# PM12_P5V5.net
KiCad netlist of a schematic drawn in Altium Designer
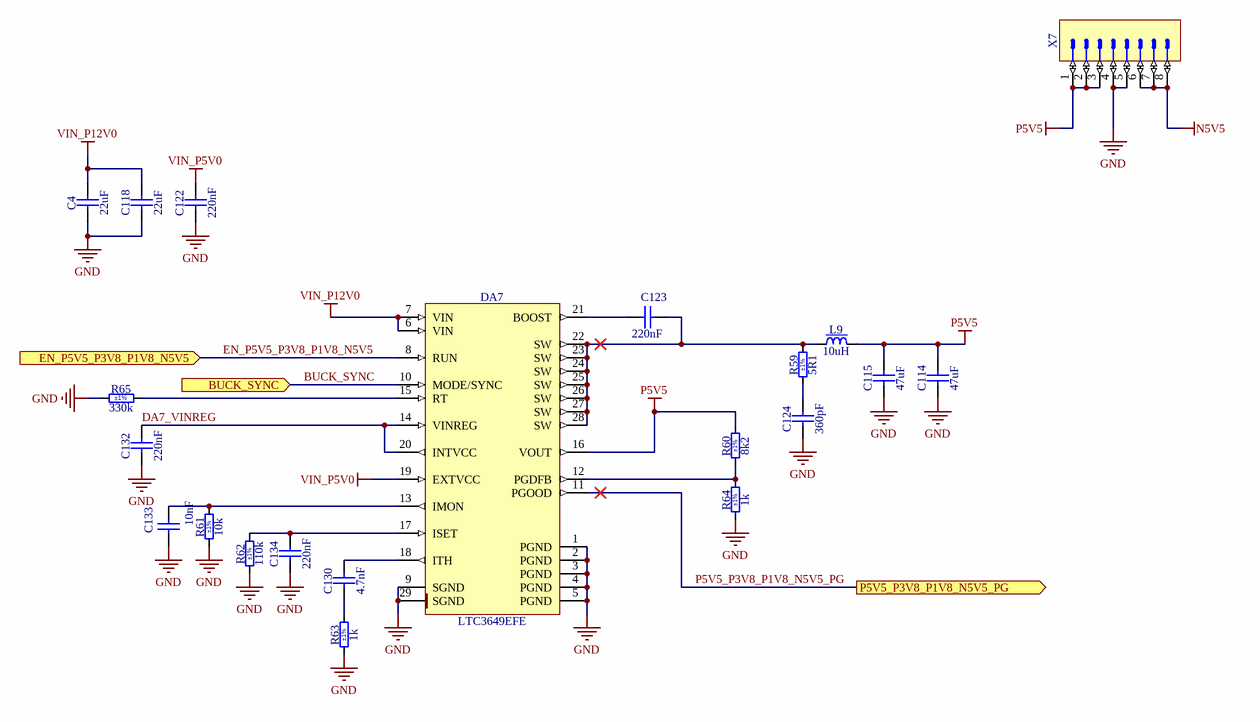
[diagram p0: PM12_P5V5.SchDoc]

(export (version "E")
  (design (tool "Eeschema 10.0.6"))
  (components
    (comp (ref "C4")
      (value "22uF")
      (footprint "CAPC3216X180N")
      (description "Non-polarised capacitor")
      (fields
        (field (name "PART NUMBER") "CC1206_22UF_25V_20%_X5R")
        (field (name "VOLTAGE") "25V")
        (field (name "AUTHOR") "CERN DEM WB")
      )
      (libsource (lib "Capacitors") (part "Capacitor - non polarized"))
    )
    (comp (ref "C114")
      (value "47uF")
      (footprint "CAPC3225X270N")
      (description "Non-polarised capacitor")
      (fields
        (field (name "PART NUMBER") "CC1210_47UF_16V_20%_X5R")
        (field (name "VOLTAGE") "16V")
        (field (name "AUTHOR") "CERN DEM MR")
      )
      (libsource (lib "Capacitors") (part "Capacitor - non polarized"))
    )
    (comp (ref "C115")
      (value "47uF")
      (footprint "CAPC3225X270N")
      (description "Non-polarised capacitor")
      (fields
        (field (name "PART NUMBER") "CC1210_47UF_16V_20%_X5R")
        (field (name "VOLTAGE") "16V")
        (field (name "AUTHOR") "CERN DEM MR")
      )
      (libsource (lib "Capacitors") (part "Capacitor - non polarized"))
    )
    (comp (ref "C118")
      (value "22uF")
      (footprint "CAPC3216X180N")
      (description "Non-polarised capacitor")
      (fields
        (field (name "PART NUMBER") "CC1206_22UF_25V_20%_X5R")
        (field (name "VOLTAGE") "25V")
        (field (name "AUTHOR") "CERN DEM WB")
      )
      (libsource (lib "Capacitors") (part "Capacitor - non polarized"))
    )
    (comp (ref "C122")
      (value "220nF")
      (footprint "CAPC2012X135N")
      (description "Non-polarised capacitor")
      (fields
        (field (name "PART NUMBER") "CC0805_220NF_50V_10%_X7R")
        (field (name "VOLTAGE") "50V")
        (field (name "AUTHOR") "CERN DEM JLC")
      )
      (libsource (lib "Capacitors") (part "Capacitor - non polarized"))
    )
    (comp (ref "C123")
      (value "220nF")
      (footprint "CAPC2012X135N")
      (description "Non-polarised capacitor")
      (fields
        (field (name "PART NUMBER") "CC0805_220NF_50V_10%_X7R")
        (field (name "VOLTAGE") "50V")
        (field (name "AUTHOR") "CERN DEM JLC")
      )
      (libsource (lib "Capacitors") (part "Capacitor - non polarized"))
    )
    (comp (ref "C124")
      (value "360pF")
      (footprint "CAPC2013X145N")
      (description "Non-polarised capacitor")
      (fields
        (field (name "PART NUMBER") "CC0805_360PF_50V_5%_C0G")
        (field (name "VOLTAGE") "50V")
        (field (name "AUTHOR") "CERN DEM HF")
      )
      (libsource (lib "Capacitors") (part "Capacitor - non polarized"))
    )
    (comp (ref "C130")
      (value "4.7nF")
      (footprint "CAPC2012X135N")
      (description "Non-polarised capacitor")
      (fields
        (field (name "PART NUMBER") "CC0805_4.7NF_50V_10%_X7R")
        (field (name "VOLTAGE") "50V")
        (field (name "AUTHOR") "CERN DEM JLC")
      )
      (libsource (lib "Capacitors") (part "Capacitor - non polarized"))
    )
    (comp (ref "C132")
      (value "220nF")
      (footprint "CAPC2012X135N")
      (description "Non-polarised capacitor")
      (fields
        (field (name "PART NUMBER") "CC0805_220NF_50V_10%_X7R")
        (field (name "VOLTAGE") "50V")
        (field (name "AUTHOR") "CERN DEM JLC")
      )
      (libsource (lib "Capacitors") (part "Capacitor - non polarized"))
    )
    (comp (ref "C133")
      (value "10nF")
      (footprint "CAPC1005X55N")
      (description "Non-polarised capacitor")
      (fields
        (field (name "PART NUMBER") "CC0402_10NF_25V_10%_X7R")
        (field (name "VOLTAGE") "25V")
        (field (name "AUTHOR") "CERN DEM JLC")
      )
      (libsource (lib "Capacitors") (part "Capacitor - non polarized"))
    )
    (comp (ref "C134")
      (value "220nF")
      (footprint "CAPC2012X135N")
      (description "Non-polarised capacitor")
      (fields
        (field (name "PART NUMBER") "CC0805_220NF_50V_10%_X7R")
        (field (name "VOLTAGE") "50V")
        (field (name "AUTHOR") "CERN DEM JLC")
      )
      (libsource (lib "Capacitors") (part "Capacitor - non polarized"))
    )
    (comp (ref "DA7")
      (value "LTC3649EFE")
      (footprint "SOP65P640X120-29N-R274X475")
      (description "60V, 4A Synchronous Step-Down Regulator with Rail-to-Rail Programmable Output")
      (fields (field (name "MANUFACTURER") "LINEAR TECHNOLOGY") (field (name "AUTHOR") "CERN DEM HF"))
      (libsource (lib "ICs And Semiconductors") (part "LTC3649XFE"))
    )
    (comp (ref "L9")
      (value "10uH")
      (footprint "IND_VISHAY_IHPL4040DZ-01")
      (description "Inductor With Core")
      (fields
        (field (name "PART NUMBER") "IND4040_10UH_20%_VISHAY_IHLP-4040DZ-01")
        (field (name "POWER") "6.8A")
        (field (name "AUTHOR") "CERN DEM HF")
      )
      (libsource (lib "Inductors & Transformers") (part "Inductor With Magnetic core"))
    )
    (comp (ref "R59")
      (value "5R1")
      (footprint "RESC2012X60N")
      (description "Resistor - 1%")
      (fields
        (field (name "TOLERANCE") "±1%")
        (field (name "PART NUMBER") "R0805_5R1_1%_0.125W_100PPM")
        (field (name "POWER") "0.125W")
        (field (name "AUTHOR") "CERN DEM HF")
      )
      (libsource (lib "Resistors") (part "Resistor - 1%"))
    )
    (comp (ref "R60")
      (value "8k2")
      (footprint "RESC2012X60N")
      (description "Resistor - 1%")
      (fields
        (field (name "TOLERANCE") "±1%")
        (field (name "PART NUMBER") "R0805_8K2_1%_0.125W_100PPM")
        (field (name "POWER") "0.125W")
        (field (name "AUTHOR") "CERN DEM JLC")
      )
      (libsource (lib "Resistors") (part "Resistor - 1%"))
    )
    (comp (ref "R61")
      (value "10k")
      (footprint "RESC1608X55N")
      (description "Resistor - 1%")
      (fields
        (field (name "TOLERANCE") "±1%")
        (field (name "PART NUMBER") "R0603_10K_1%_0.1W_100PPM")
        (field (name "POWER") "0.1W")
        (field (name "AUTHOR") "CERN DEM JLC")
      )
      (libsource (lib "Resistors") (part "Resistor - 1%"))
    )
    (comp (ref "R62")
      (value "110k")
      (footprint "RESC2012X60N")
      (description "Resistor - 1%")
      (fields
        (field (name "TOLERANCE") "±1%")
        (field (name "PART NUMBER") "R0805_110K_1%_0.125W_100PPM")
        (field (name "POWER") "0.125W")
        (field (name "AUTHOR") "CERN DEM JLC")
      )
      (libsource (lib "Resistors") (part "Resistor - 1%"))
    )
    (comp (ref "R63")
      (value "1k")
      (footprint "RESC1005X40N")
      (description "Resistor - 1%")
      (fields
        (field (name "TOLERANCE") "±1%")
        (field (name "PART NUMBER") "R0402_1K_1%_0.0625W_100PPM")
        (field (name "POWER") "0.0625W")
        (field (name "AUTHOR") "CERN DEM JLC")
      )
      (libsource (lib "Resistors") (part "Resistor - 1%"))
    )
    (comp (ref "R64")
      (value "1k")
      (footprint "RESC1005X40N")
      (description "Resistor - 1%")
      (fields
        (field (name "TOLERANCE") "±1%")
        (field (name "PART NUMBER") "R0402_1K_1%_0.0625W_100PPM")
        (field (name "POWER") "0.0625W")
        (field (name "AUTHOR") "CERN DEM JLC")
      )
      (libsource (lib "Resistors") (part "Resistor - 1%"))
    )
    (comp (ref "R65")
      (value "330k")
      (footprint "RESC2012X60N")
      (description "Resistor - 1%")
      (fields
        (field (name "TOLERANCE") "±1%")
        (field (name "PART NUMBER") "R0805_330K_1%_0.125W_100PPM")
        (field (name "POWER") "0.125W")
        (field (name "AUTHOR") "CERN DEM JLC")
      )
      (libsource (lib "Resistors") (part "Resistor - 1%"))
    )
    (comp (ref "X7")
      (value "Header 8")
      (footprint "SAMTEC_DW-08-09-L-S-470")
      (description "Connector 8 Male")
      (fields
        (field (name "PART NUMBER") "SAMTEC_DW-08-09-L-S-470")
        (field (name "MANUFACTURER") "SAMTEC")
        (field (name "AUTHOR") "CERN DEM HF")
      )
      (libsource (lib "Connectors") (part "Connector 8 Male"))
    )
  )
  (nets
    (net (code "1") (name "/BUCK_SYNC") (class "Default")
      (node (ref "DA7") (pin "10") (pinfunction "MODE/SYNC_10") (pintype "input"))
    )
    (net (code "2") (name "/DA7_VINREG") (class "Default")
      (node (ref "C132") (pin "2") (pinfunction "2_2") (pintype "passive"))
      (node (ref "DA7") (pin "14") (pinfunction "VINREG_14") (pintype "input"))
      (node (ref "DA7") (pin "20") (pinfunction "INTVCC_20") (pintype "output"))
    )
    (net (code "3") (name "/EN_P5V5_P3V8_P1V8_N5V5") (class "Default")
      (node (ref "DA7") (pin "8") (pinfunction "RUN_8") (pintype "input"))
    )
    (net (code "4") (name "/P5V5_P3V8_P1V8_N5V5_PG") (class "Default")
      (node (ref "DA7") (pin "11") (pinfunction "PGOOD_11") (pintype "output"))
    )
    (net (code "5") (name "GND") (class "Default")
      (node (ref "C114") (pin "1") (pinfunction "1_1") (pintype "passive"))
      (node (ref "C115") (pin "1") (pinfunction "1_1") (pintype "passive"))
      (node (ref "C118") (pin "1") (pinfunction "1_1") (pintype "passive"))
      (node (ref "C122") (pin "1") (pinfunction "1_1") (pintype "passive"))
      (node (ref "C124") (pin "1") (pinfunction "1_1") (pintype "passive"))
      (node (ref "C132") (pin "1") (pinfunction "1_1") (pintype "passive"))
      (node (ref "C133") (pin "2") (pinfunction "2_2") (pintype "passive"))
      (node (ref "C134") (pin "1") (pinfunction "1_1") (pintype "passive"))
      (node (ref "C4") (pin "1") (pinfunction "1_1") (pintype "passive"))
      (node (ref "DA7") (pin "1") (pinfunction "PGND_1") (pintype "power_in"))
      (node (ref "DA7") (pin "2") (pinfunction "PGND_2") (pintype "power_in"))
      (node (ref "DA7") (pin "29") (pinfunction "SGND_29") (pintype "power_in"))
      (node (ref "DA7") (pin "3") (pinfunction "PGND_3") (pintype "power_in"))
      (node (ref "DA7") (pin "4") (pinfunction "PGND_4") (pintype "power_in"))
      (node (ref "DA7") (pin "5") (pinfunction "PGND_5") (pintype "power_in"))
      (node (ref "DA7") (pin "9") (pinfunction "SGND_9") (pintype "power_in"))
      (node (ref "R61") (pin "1") (pinfunction "1_1") (pintype "passive"))
      (node (ref "R62") (pin "1") (pinfunction "1_1") (pintype "passive"))
      (node (ref "R63") (pin "1") (pinfunction "1_1") (pintype "passive"))
      (node (ref "R64") (pin "1") (pinfunction "1_1") (pintype "passive"))
      (node (ref "R65") (pin "1") (pinfunction "1_1") (pintype "passive"))
      (node (ref "X7") (pin "4") (pinfunction "4_4") (pintype "bidirectional"))
      (node (ref "X7") (pin "5") (pinfunction "5_5") (pintype "bidirectional"))
    )
    (net (code "6") (name "N5V5") (class "Default")
      (node (ref "X7") (pin "6") (pinfunction "6_6") (pintype "bidirectional"))
      (node (ref "X7") (pin "7") (pinfunction "7_7") (pintype "bidirectional"))
      (node (ref "X7") (pin "8") (pinfunction "8_8") (pintype "bidirectional"))
    )
    (net (code "7") (name "Net-(C123-Pad2)") (class "Default")
      (node (ref "C123") (pin "2") (pinfunction "2_2") (pintype "passive"))
      (node (ref "DA7") (pin "22") (pinfunction "SW_22") (pintype "output"))
      (node (ref "DA7") (pin "23") (pinfunction "SW_23") (pintype "output"))
      (node (ref "DA7") (pin "24") (pinfunction "SW_24") (pintype "output"))
      (node (ref "DA7") (pin "25") (pinfunction "SW_25") (pintype "output"))
      (node (ref "DA7") (pin "26") (pinfunction "SW_26") (pintype "output"))
      (node (ref "DA7") (pin "27") (pinfunction "SW_27") (pintype "output"))
      (node (ref "DA7") (pin "28") (pinfunction "SW_28") (pintype "output"))
      (node (ref "L9") (pin "1") (pinfunction "1_1") (pintype "passive"))
      (node (ref "R59") (pin "2") (pinfunction "2_2") (pintype "passive"))
    )
    (net (code "8") (name "Net-(C124-Pad2)") (class "Default")
      (node (ref "C124") (pin "2") (pinfunction "2_2") (pintype "passive"))
      (node (ref "R59") (pin "1") (pinfunction "1_1") (pintype "passive"))
    )
    (net (code "9") (name "Net-(C130-Pad1)") (class "Default")
      (node (ref "C130") (pin "1") (pinfunction "1_1") (pintype "passive"))
      (node (ref "R63") (pin "2") (pinfunction "2_2") (pintype "passive"))
    )
    (net (code "10") (name "Net-(DA7-BOOST)") (class "Default")
      (node (ref "C123") (pin "1") (pinfunction "1_1") (pintype "passive"))
      (node (ref "DA7") (pin "21") (pinfunction "BOOST_21") (pintype "output"))
    )
    (net (code "11") (name "Net-(DA7-IMON)") (class "Default")
      (node (ref "C133") (pin "1") (pinfunction "1_1") (pintype "passive"))
      (node (ref "DA7") (pin "13") (pinfunction "IMON_13") (pintype "output"))
      (node (ref "R61") (pin "2") (pinfunction "2_2") (pintype "passive"))
    )
    (net (code "12") (name "Net-(DA7-ISET)") (class "Default")
      (node (ref "C134") (pin "2") (pinfunction "2_2") (pintype "passive"))
      (node (ref "DA7") (pin "17") (pinfunction "ISET_17") (pintype "input"))
      (node (ref "R62") (pin "2") (pinfunction "2_2") (pintype "passive"))
    )
    (net (code "13") (name "Net-(DA7-ITH)") (class "Default")
      (node (ref "C130") (pin "2") (pinfunction "2_2") (pintype "passive"))
      (node (ref "DA7") (pin "18") (pinfunction "ITH_18") (pintype "output"))
    )
    (net (code "14") (name "Net-(DA7-PGDFB)") (class "Default")
      (node (ref "DA7") (pin "12") (pinfunction "PGDFB_12") (pintype "output"))
      (node (ref "R60") (pin "1") (pinfunction "1_1") (pintype "passive"))
      (node (ref "R64") (pin "2") (pinfunction "2_2") (pintype "passive"))
    )
    (net (code "15") (name "Net-(DA7-RT)") (class "Default")
      (node (ref "DA7") (pin "15") (pinfunction "RT_15") (pintype "input"))
      (node (ref "R65") (pin "2") (pinfunction "2_2") (pintype "passive"))
    )
    (net (code "16") (name "P5V5") (class "Default")
      (node (ref "C114") (pin "2") (pinfunction "2_2") (pintype "passive"))
      (node (ref "C115") (pin "2") (pinfunction "2_2") (pintype "passive"))
      (node (ref "DA7") (pin "16") (pinfunction "VOUT_16") (pintype "output"))
      (node (ref "L9") (pin "2") (pinfunction "2_2") (pintype "passive"))
      (node (ref "R60") (pin "2") (pinfunction "2_2") (pintype "passive"))
      (node (ref "X7") (pin "1") (pinfunction "1_1") (pintype "bidirectional"))
      (node (ref "X7") (pin "2") (pinfunction "2_2") (pintype "bidirectional"))
      (node (ref "X7") (pin "3") (pinfunction "3_3") (pintype "bidirectional"))
    )
    (net (code "17") (name "VIN_P5V0") (class "Default")
      (node (ref "C122") (pin "2") (pinfunction "2_2") (pintype "passive"))
      (node (ref "DA7") (pin "19") (pinfunction "EXTVCC_19") (pintype "input"))
    )
    (net (code "18") (name "VIN_P12V0") (class "Default")
      (node (ref "C118") (pin "2") (pinfunction "2_2") (pintype "passive"))
      (node (ref "C4") (pin "2") (pinfunction "2_2") (pintype "passive"))
      (node (ref "DA7") (pin "6") (pinfunction "VIN_6") (pintype "input"))
      (node (ref "DA7") (pin "7") (pinfunction "VIN_7") (pintype "input"))
    )
  )
)
